# Prototype_Board.net
KiCad netlist of a schematic drawn in EAGLE
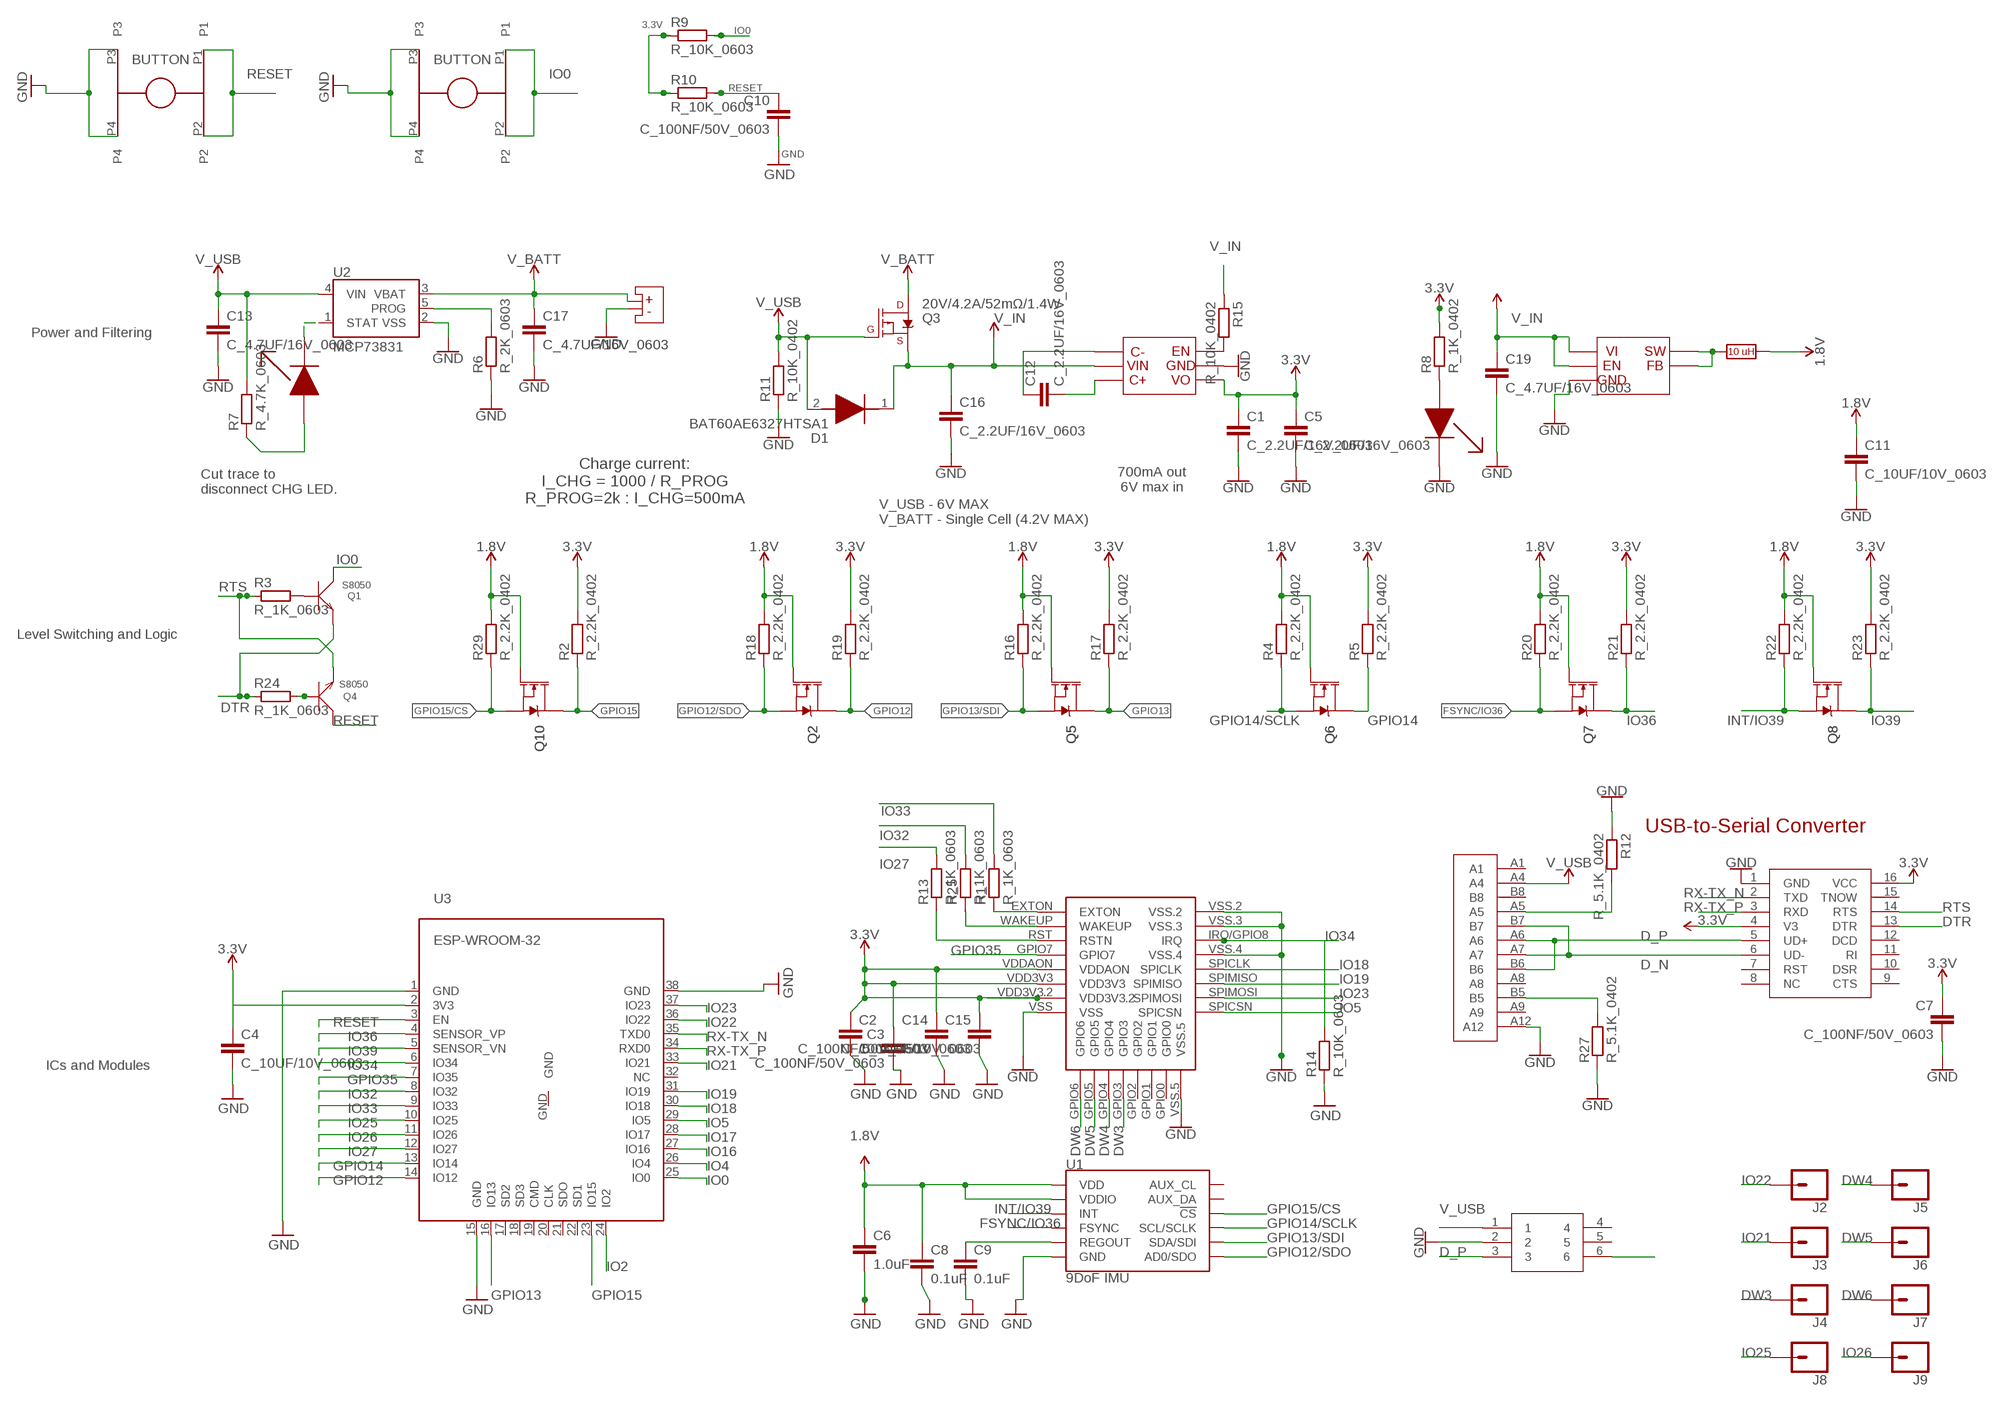
[diagram p0: schematic, sheet 1]

(export (version "E")
  (design (tool "Eeschema 10.0.6"))
  (components
    (comp (ref "C1")
      (value "C_2.2UF/16V_0603")
      (footprint "eagle-import:C0603")
      (fields (field (name "LCSC_PART") "C23630"))
      (libsource (lib "eagle-import") (part "C__06032.2UF/16V"))
    )
    (comp (ref "C2")
      (value "C_10UF/10V_0603")
      (footprint "eagle-import:C0603")
      (fields (field (name "LCSC_PART") "C19702"))
      (libsource (lib "eagle-import") (part "C__060310UF/10V"))
    )
    (comp (ref "C3")
      (value "C_100NF/50V_0603")
      (footprint "eagle-import:C0603")
      (fields (field (name "LCSC_PART") "C14663"))
      (libsource (lib "eagle-import") (part "C__0603100NF/50V"))
    )
    (comp (ref "C4")
      (value "C_10UF/10V_0603")
      (footprint "eagle-import:C0603")
      (fields (field (name "LCSC_PART") "C19702"))
      (libsource (lib "eagle-import") (part "C__060310UF/10V"))
    )
    (comp (ref "C5")
      (value "C_2.2UF/16V_0603")
      (footprint "eagle-import:C0603")
      (fields (field (name "LCSC_PART") "C23630"))
      (libsource (lib "eagle-import") (part "C__06032.2UF/16V"))
    )
    (comp (ref "C6")
      (value "1.0uF")
      (footprint "eagle-import:0603")
      (libsource (lib "eagle-import") (part "1.0UF-0603-16V-10%-X7R"))
    )
    (comp (ref "C7")
      (value "C_100NF/50V_0603")
      (footprint "eagle-import:C0603")
      (fields (field (name "LCSC_PART") "C14663"))
      (libsource (lib "eagle-import") (part "C__0603100NF/50V"))
    )
    (comp (ref "C8")
      (value "0.1uF")
      (footprint "eagle-import:0603")
      (libsource (lib "eagle-import") (part "0.1UF-0603-25V-5%"))
    )
    (comp (ref "C9")
      (value "0.1uF")
      (footprint "eagle-import:0603")
      (libsource (lib "eagle-import") (part "0.1UF-0603-25V-5%"))
    )
    (comp (ref "C10")
      (value "C_100NF/50V_0603")
      (footprint "eagle-import:C0603")
      (fields (field (name "LCSC_PART") "C14663"))
      (libsource (lib "eagle-import") (part "C__0603100NF/50V"))
    )
    (comp (ref "C11")
      (value "C_10UF/10V_0603")
      (footprint "eagle-import:C0603")
      (fields (field (name "LCSC_PART") "C19702"))
      (libsource (lib "eagle-import") (part "C__060310UF/10V"))
    )
    (comp (ref "C12")
      (value "C_2.2UF/16V_0603")
      (footprint "eagle-import:C0603")
      (fields (field (name "LCSC_PART") "C23630"))
      (libsource (lib "eagle-import") (part "C__06032.2UF/16V"))
    )
    (comp (ref "C13")
      (value "C_4.7UF/16V_0603")
      (footprint "eagle-import:C0603")
      (fields (field (name "LCSC_PART") "C19666"))
      (libsource (lib "eagle-import") (part "C__06034.7UF/16V"))
    )
    (comp (ref "C14")
      (value "C_100NF/50V_0603")
      (footprint "eagle-import:C0603")
      (fields (field (name "LCSC_PART") "C14663"))
      (libsource (lib "eagle-import") (part "C__0603100NF/50V"))
    )
    (comp (ref "C15")
      (value "C_100NF/50V_0603")
      (footprint "eagle-import:C0603")
      (fields (field (name "LCSC_PART") "C14663"))
      (libsource (lib "eagle-import") (part "C__0603100NF/50V"))
    )
    (comp (ref "C16")
      (value "C_2.2UF/16V_0603")
      (footprint "eagle-import:C0603")
      (fields (field (name "LCSC_PART") "C23630"))
      (libsource (lib "eagle-import") (part "C__06032.2UF/16V"))
    )
    (comp (ref "C17")
      (value "C_4.7UF/16V_0603")
      (footprint "eagle-import:C0603")
      (fields (field (name "LCSC_PART") "C19666"))
      (libsource (lib "eagle-import") (part "C__06034.7UF/16V"))
    )
    (comp (ref "C19")
      (value "C_4.7UF/16V_0603")
      (footprint "eagle-import:C0603")
      (fields (field (name "LCSC_PART") "C19666"))
      (libsource (lib "eagle-import") (part "C__06034.7UF/16V"))
    )
    (comp (ref "D1")
      (value "BAT60AE6327HTSA1")
      (footprint "eagle-import:SOD2513X110N")
      (fields (field (name "MOUSER_PART_NUMBER") "726-BAT60AE6327HTSA1"))
      (libsource (lib "eagle-import") (part "BAT60AE6327HTSA1"))
    )
    (comp (ref "J2")
      (value "CONN_01PTH_2MM")
      (footprint "eagle-import:1X01_2MM")
      (libsource (lib "eagle-import") (part "CONN_01PTH_2MM"))
    )
    (comp (ref "J3")
      (value "CONN_01PTH_2MM")
      (footprint "eagle-import:1X01_2MM")
      (libsource (lib "eagle-import") (part "CONN_01PTH_2MM"))
    )
    (comp (ref "J4")
      (value "CONN_01PTH_2MM")
      (footprint "eagle-import:1X01_2MM")
      (libsource (lib "eagle-import") (part "CONN_01PTH_2MM"))
    )
    (comp (ref "J5")
      (value "CONN_01PTH_2MM")
      (footprint "eagle-import:1X01_2MM")
      (libsource (lib "eagle-import") (part "CONN_01PTH_2MM"))
    )
    (comp (ref "J6")
      (value "CONN_01PTH_2MM")
      (footprint "eagle-import:1X01_2MM")
      (libsource (lib "eagle-import") (part "CONN_01PTH_2MM"))
    )
    (comp (ref "J7")
      (value "CONN_01PTH_2MM")
      (footprint "eagle-import:1X01_2MM")
      (libsource (lib "eagle-import") (part "CONN_01PTH_2MM"))
    )
    (comp (ref "J8")
      (value "CONN_01PTH_2MM")
      (footprint "eagle-import:1X01_2MM")
      (libsource (lib "eagle-import") (part "CONN_01PTH_2MM"))
    )
    (comp (ref "J9")
      (value "CONN_01PTH_2MM")
      (footprint "eagle-import:1X01_2MM")
      (libsource (lib "eagle-import") (part "CONN_01PTH_2MM"))
    )
    (comp (ref "Q1")
      (value "S8050")
      (footprint "eagle-import:SOT23")
      (libsource (lib "eagle-import") (part "TRANSISTOR-NPN-SOT23"))
    )
    (comp (ref "Q2")
      (value "20V/0.2A/8MHz/1.2Ω/1Vth")
      (footprint "eagle-import:SOT-416FL")
      (libsource (lib "eagle-import") (part "MOSFET-NCH-RE1C002UN"))
    )
    (comp (ref "Q3")
      (value "20V/4.2A/52mΩ/1.4W")
      (footprint "eagle-import:SOT23-3@1")
      (libsource (lib "eagle-import") (part "MOSFET_PCH-DMG2305UX-7"))
    )
    (comp (ref "Q4")
      (value "S8050")
      (footprint "eagle-import:SOT23")
      (libsource (lib "eagle-import") (part "TRANSISTOR-NPN-SOT23"))
    )
    (comp (ref "Q5")
      (value "20V/0.2A/8MHz/1.2Ω/1Vth")
      (footprint "eagle-import:SOT-416FL")
      (libsource (lib "eagle-import") (part "MOSFET-NCH-RE1C002UN"))
    )
    (comp (ref "Q6")
      (value "20V/0.2A/8MHz/1.2Ω/1Vth")
      (footprint "eagle-import:SOT-416FL")
      (libsource (lib "eagle-import") (part "MOSFET-NCH-RE1C002UN"))
    )
    (comp (ref "Q7")
      (value "20V/0.2A/8MHz/1.2Ω/1Vth")
      (footprint "eagle-import:SOT-416FL")
      (libsource (lib "eagle-import") (part "MOSFET-NCH-RE1C002UN"))
    )
    (comp (ref "Q8")
      (value "20V/0.2A/8MHz/1.2Ω/1Vth")
      (footprint "eagle-import:SOT-416FL")
      (libsource (lib "eagle-import") (part "MOSFET-NCH-RE1C002UN"))
    )
    (comp (ref "Q10")
      (value "20V/0.2A/8MHz/1.2Ω/1Vth")
      (footprint "eagle-import:SOT-416FL")
      (libsource (lib "eagle-import") (part "MOSFET-NCH-RE1C002UN"))
    )
    (comp (ref "R1")
      (value "R_1K_0603")
      (footprint "eagle-import:R0603")
      (fields (field (name "LCSC_PART") "C21190"))
      (libsource (lib "eagle-import") (part "R__06031K"))
    )
    (comp (ref "R2")
      (value "R_2.2K_0402")
      (footprint "eagle-import:R0402")
      (fields (field (name "LCSC_PART") "C25879"))
      (libsource (lib "eagle-import") (part "R__04022.2K"))
    )
    (comp (ref "R3")
      (value "R_1K_0603")
      (footprint "eagle-import:R0603")
      (fields (field (name "LCSC_PART") "C21190"))
      (libsource (lib "eagle-import") (part "R__06031K"))
    )
    (comp (ref "R4")
      (value "R_2.2K_0402")
      (footprint "eagle-import:R0402")
      (fields (field (name "LCSC_PART") "C25879"))
      (libsource (lib "eagle-import") (part "R__04022.2K"))
    )
    (comp (ref "R5")
      (value "R_2.2K_0402")
      (footprint "eagle-import:R0402")
      (fields (field (name "LCSC_PART") "C25879"))
      (libsource (lib "eagle-import") (part "R__04022.2K"))
    )
    (comp (ref "R6")
      (value "R_2K_0603")
      (footprint "eagle-import:R0603")
      (fields (field (name "LCSC_PART") "C22975"))
      (libsource (lib "eagle-import") (part "R__06032K"))
    )
    (comp (ref "R7")
      (value "R_4.7K_0603")
      (footprint "eagle-import:R0603")
      (fields (field (name "LCSC_PART") "C23162"))
      (libsource (lib "eagle-import") (part "R__06034.7K"))
    )
    (comp (ref "R8")
      (value "R_1K_0402")
      (footprint "eagle-import:R0402")
      (fields (field (name "LCSC_PART") "C11702"))
      (libsource (lib "eagle-import") (part "R__04021K"))
    )
    (comp (ref "R9")
      (value "R_10K_0603")
      (footprint "eagle-import:R0603")
      (fields (field (name "LCSC_PART") "C25804"))
      (libsource (lib "eagle-import") (part "R__060310K"))
    )
    (comp (ref "R10")
      (value "R_10K_0603")
      (footprint "eagle-import:R0603")
      (fields (field (name "LCSC_PART") "C25804"))
      (libsource (lib "eagle-import") (part "R__060310K"))
    )
    (comp (ref "R11")
      (value "R_10K_0402")
      (footprint "eagle-import:R0402")
      (fields (field (name "LCSC_PART") "C25744"))
      (libsource (lib "eagle-import") (part "R__040210K"))
    )
    (comp (ref "R12")
      (value "R_5.1K_0402")
      (footprint "eagle-import:R0402")
      (fields (field (name "LCSC_PART") "C25905"))
      (libsource (lib "eagle-import") (part "R__04025.1K"))
    )
    (comp (ref "R13")
      (value "R_1K_0603")
      (footprint "eagle-import:R0603")
      (fields (field (name "LCSC_PART") "C21190"))
      (libsource (lib "eagle-import") (part "R__06031K"))
    )
    (comp (ref "R14")
      (value "R_10K_0603")
      (footprint "eagle-import:R0603")
      (fields (field (name "LCSC_PART") "C25804"))
      (libsource (lib "eagle-import") (part "R__060310K"))
    )
    (comp (ref "R15")
      (value "R_10K_0402")
      (footprint "eagle-import:R0402")
      (fields (field (name "LCSC_PART") "C25744"))
      (libsource (lib "eagle-import") (part "R__040210K"))
    )
    (comp (ref "R16")
      (value "R_2.2K_0402")
      (footprint "eagle-import:R0402")
      (fields (field (name "LCSC_PART") "C25879"))
      (libsource (lib "eagle-import") (part "R__04022.2K"))
    )
    (comp (ref "R17")
      (value "R_2.2K_0402")
      (footprint "eagle-import:R0402")
      (fields (field (name "LCSC_PART") "C25879"))
      (libsource (lib "eagle-import") (part "R__04022.2K"))
    )
    (comp (ref "R18")
      (value "R_2.2K_0402")
      (footprint "eagle-import:R0402")
      (fields (field (name "LCSC_PART") "C25879"))
      (libsource (lib "eagle-import") (part "R__04022.2K"))
    )
    (comp (ref "R19")
      (value "R_2.2K_0402")
      (footprint "eagle-import:R0402")
      (fields (field (name "LCSC_PART") "C25879"))
      (libsource (lib "eagle-import") (part "R__04022.2K"))
    )
    (comp (ref "R20")
      (value "R_2.2K_0402")
      (footprint "eagle-import:R0402")
      (fields (field (name "LCSC_PART") "C25879"))
      (libsource (lib "eagle-import") (part "R__04022.2K"))
    )
    (comp (ref "R21")
      (value "R_2.2K_0402")
      (footprint "eagle-import:R0402")
      (fields (field (name "LCSC_PART") "C25879"))
      (libsource (lib "eagle-import") (part "R__04022.2K"))
    )
    (comp (ref "R22")
      (value "R_2.2K_0402")
      (footprint "eagle-import:R0402")
      (fields (field (name "LCSC_PART") "C25879"))
      (libsource (lib "eagle-import") (part "R__04022.2K"))
    )
    (comp (ref "R23")
      (value "R_2.2K_0402")
      (footprint "eagle-import:R0402")
      (fields (field (name "LCSC_PART") "C25879"))
      (libsource (lib "eagle-import") (part "R__04022.2K"))
    )
    (comp (ref "R24")
      (value "R_1K_0603")
      (footprint "eagle-import:R0603")
      (fields (field (name "LCSC_PART") "C21190"))
      (libsource (lib "eagle-import") (part "R__06031K"))
    )
    (comp (ref "R25")
      (value "R_1K_0603")
      (footprint "eagle-import:R0603")
      (fields (field (name "LCSC_PART") "C21190"))
      (libsource (lib "eagle-import") (part "R__06031K"))
    )
    (comp (ref "R27")
      (value "R_5.1K_0402")
      (footprint "eagle-import:R0402")
      (fields (field (name "LCSC_PART") "C25905"))
      (libsource (lib "eagle-import") (part "R__04025.1K"))
    )
    (comp (ref "R29")
      (value "R_2.2K_0402")
      (footprint "eagle-import:R0402")
      (fields (field (name "LCSC_PART") "C25879"))
      (libsource (lib "eagle-import") (part "R__04022.2K"))
    )
    (comp (ref "U$1")
      (value "K2-6639SP-C4SC-04_C83206")
      (footprint "eagle-import:K2-6639SP-C4SC-04")
      (libsource (lib "eagle-import") (part "K2-6639SP-C4SC-04_C83206"))
    )
    (comp (ref "U$2")
      (value "MLF2012")
      (footprint "eagle-import:MLF2012")
      (libsource (lib "eagle-import") (part "MLF2012"))
    )
    (comp (ref "U$3")
      (value "K2-6639SP-C4SC-04_C83206")
      (footprint "eagle-import:K2-6639SP-C4SC-04")
      (libsource (lib "eagle-import") (part "K2-6639SP-C4SC-04_C83206"))
    )
    (comp (ref "U$4")
      (value "TPS62202DBVR")
      (footprint "eagle-import:TPS62202DBVR")
      (libsource (lib "eagle-import") (part "TPS62202DBVR"))
    )
    (comp (ref "U$5")
      (value "HE9008M6R")
      (footprint "eagle-import:HE9008M6R")
      (libsource (lib "eagle-import") (part "HE9008M6R"))
    )
    (comp (ref "U$6")
      (value "19-217/GHC-YR1S2/3T")
      (footprint "eagle-import:19-217_GHC-YR1S2_3T")
      (libsource (lib "eagle-import") (part "19-217/GHC-YR1S2/3T"))
    )
    (comp (ref "U$7")
      (value "TPSMF05CT1G")
      (footprint "eagle-import:TPSMF05CT1G")
      (libsource (lib "eagle-import") (part "TPSMF05CT1G"))
    )
    (comp (ref "U$8")
      (value "SM02B_PASS_TB_LF")
      (footprint "eagle-import:SM02B_PASS_TB_LF")
      (libsource (lib "eagle-import") (part "SM02B_PASS_TB_LF"))
    )
    (comp (ref "U$9")
      (value "19-217/GHC-YR1S2/3T")
      (footprint "eagle-import:19-217_GHC-YR1S2_3T")
      (libsource (lib "eagle-import") (part "19-217/GHC-YR1S2/3T"))
    )
    (comp (ref "U$10")
      (value "USBC19")
      (footprint "eagle-import:USBC19")
      (libsource (lib "eagle-import") (part "USBC19"))
    )
    (comp (ref "U$11")
      (value "CH340B")
      (footprint "eagle-import:SOP-16")
      (libsource (lib "eagle-import") (part "CH340B"))
    )
    (comp (ref "U1")
      (value "9DoF IMU")
      (footprint "eagle-import:QFN24-3X3")
      (libsource (lib "eagle-import") (part "ICM-20948"))
    )
    (comp (ref "U2")
      (value "MCP73831")
      (footprint "eagle-import:SOT23-5")
      (libsource (lib "eagle-import") (part "MCP73831"))
    )
    (comp (ref "U3")
      (value "ESP-WROOM-32")
      (footprint "eagle-import:ESP-WROOM-32")
      (libsource (lib "eagle-import") (part "ESP-WROOM-32"))
    )
    (comp (ref "U5")
      (value "DWM1000")
      (footprint "eagle-import:DWM1000")
      (libsource (lib "eagle-import") (part "DWM1000"))
    )
  )
  (nets
    (net (code "1") (name "/DTR") (class "Default")
      (node (ref "Q1") (pin "2") (pinfunction "E_2") (pintype "passive"))
      (node (ref "R24") (pin "1") (pinfunction "1_1") (pintype "passive"))
      (node (ref "U$11") (pin "13") (pinfunction "DTR_13") (pintype "bidirectional"))
    )
    (net (code "2") (name "/DW3") (class "Default")
      (node (ref "J4") (pin "1") (pinfunction "1_1") (pintype "passive"))
      (node (ref "U5") (pin "GPIO3") (pinfunction "GPIO3_GPIO3") (pintype "bidirectional"))
    )
    (net (code "3") (name "/DW4") (class "Default")
      (node (ref "J5") (pin "1") (pinfunction "1_1") (pintype "passive"))
      (node (ref "U5") (pin "GPIO4") (pinfunction "GPIO4_GPIO4") (pintype "bidirectional"))
    )
    (net (code "4") (name "/DW5") (class "Default")
      (node (ref "J6") (pin "1") (pinfunction "1_1") (pintype "passive"))
      (node (ref "U5") (pin "GPIO5") (pinfunction "GPIO5_GPIO5") (pintype "bidirectional"))
    )
    (net (code "5") (name "/DW6") (class "Default")
      (node (ref "J7") (pin "1") (pinfunction "1_1") (pintype "passive"))
      (node (ref "U5") (pin "GPIO6") (pinfunction "GPIO6_GPIO6") (pintype "bidirectional"))
    )
    (net (code "6") (name "/D_N") (class "Default")
      (node (ref "U$10") (pin "A7") (pinfunction "A7_A7") (pintype "bidirectional"))
      (node (ref "U$10") (pin "B7") (pinfunction "B7_B7") (pintype "bidirectional"))
      (node (ref "U$11") (pin "6") (pinfunction "UD-_6") (pintype "bidirectional"))
      (node (ref "U$7") (pin "6") (pinfunction "6_6") (pintype "bidirectional"))
    )
    (net (code "7") (name "/D_P") (class "Default")
      (node (ref "U$10") (pin "A6") (pinfunction "A6_A6") (pintype "bidirectional"))
      (node (ref "U$10") (pin "B6") (pinfunction "B6_B6") (pintype "bidirectional"))
      (node (ref "U$11") (pin "5") (pinfunction "UD+_5") (pintype "bidirectional"))
      (node (ref "U$7") (pin "3") (pinfunction "3_3") (pintype "bidirectional"))
    )
    (net (code "8") (name "/GPIO14") (class "Default")
      (node (ref "Q6") (pin "3") (pinfunction "D_3") (pintype "bidirectional"))
      (node (ref "R5") (pin "1") (pinfunction "1_1") (pintype "passive"))
      (node (ref "U3") (pin "13") (pinfunction "IO14_13") (pintype "bidirectional"))
    )
    (net (code "9") (name "/GPIO14{slash}SCLK") (class "Default")
      (node (ref "Q6") (pin "2") (pinfunction "S_2") (pintype "bidirectional"))
      (node (ref "R4") (pin "1") (pinfunction "1_1") (pintype "passive"))
      (node (ref "U1") (pin "23") (pinfunction "SCL/SCLK_23") (pintype "bidirectional"))
    )
    (net (code "10") (name "/GPIO35") (class "Default")
      (node (ref "U3") (pin "7") (pinfunction "IO35_7") (pintype "bidirectional"))
      (node (ref "U5") (pin "GPIO7") (pinfunction "GPIO7_GPIO7") (pintype "bidirectional"))
    )
    (net (code "11") (name "/INT{slash}IO39") (class "Default")
      (node (ref "Q8") (pin "2") (pinfunction "S_2") (pintype "bidirectional"))
      (node (ref "R22") (pin "1") (pinfunction "1_1") (pintype "passive"))
      (node (ref "U1") (pin "12") (pinfunction "INT_12") (pintype "bidirectional"))
    )
    (net (code "12") (name "/IO0") (class "Default")
      (node (ref "Q1") (pin "3") (pinfunction "C_3") (pintype "passive"))
      (node (ref "R9") (pin "2") (pinfunction "2_2") (pintype "passive"))
      (node (ref "U$3") (pin "P1") (pinfunction "P1_P1") (pintype "bidirectional"))
      (node (ref "U$3") (pin "P2") (pinfunction "P2_P2") (pintype "bidirectional"))
      (node (ref "U3") (pin "25") (pinfunction "IO0_25") (pintype "bidirectional"))
    )
    (net (code "13") (name "/IO2") (class "Default")
      (node (ref "U3") (pin "24") (pinfunction "IO2_24") (pintype "bidirectional"))
    )
    (net (code "14") (name "/IO4") (class "Default")
      (node (ref "U3") (pin "26") (pinfunction "IO4_26") (pintype "bidirectional"))
    )
    (net (code "15") (name "/IO5") (class "Default")
      (node (ref "U3") (pin "29") (pinfunction "IO5_29") (pintype "bidirectional"))
      (node (ref "U5") (pin "SPICSN") (pinfunction "SPICSN_SPICSN") (pintype "bidirectional"))
    )
    (net (code "16") (name "/IO16") (class "Default")
      (node (ref "U3") (pin "27") (pinfunction "IO16_27") (pintype "bidirectional"))
    )
    (net (code "17") (name "/IO17") (class "Default")
      (node (ref "U3") (pin "28") (pinfunction "IO17_28") (pintype "bidirectional"))
    )
    (net (code "18") (name "/IO18") (class "Default")
      (node (ref "U3") (pin "30") (pinfunction "IO18_30") (pintype "bidirectional"))
      (node (ref "U5") (pin "SPICLK") (pinfunction "SPICLK_SPICLK") (pintype "bidirectional"))
    )
    (net (code "19") (name "/IO19") (class "Default")
      (node (ref "U3") (pin "31") (pinfunction "IO19_31") (pintype "bidirectional"))
      (node (ref "U5") (pin "SPIMISO") (pinfunction "SPIMISO_SPIMISO") (pintype "bidirectional"))
    )
    (net (code "20") (name "/IO21") (class "Default")
      (node (ref "J3") (pin "1") (pinfunction "1_1") (pintype "passive"))
      (node (ref "U3") (pin "33") (pinfunction "IO21_33") (pintype "bidirectional"))
    )
    (net (code "21") (name "/IO22") (class "Default")
      (node (ref "J2") (pin "1") (pinfunction "1_1") (pintype "passive"))
      (node (ref "U3") (pin "36") (pinfunction "IO22_36") (pintype "bidirectional"))
    )
    (net (code "22") (name "/IO23") (class "Default")
      (node (ref "U3") (pin "37") (pinfunction "IO23_37") (pintype "bidirectional"))
      (node (ref "U5") (pin "SPIMOSI") (pinfunction "SPIMOSI_SPIMOSI") (pintype "bidirectional"))
    )
    (net (code "23") (name "/IO25") (class "Default")
      (node (ref "J8") (pin "1") (pinfunction "1_1") (pintype "passive"))
      (node (ref "U3") (pin "10") (pinfunction "IO25_10") (pintype "bidirectional"))
    )
    (net (code "24") (name "/IO26") (class "Default")
      (node (ref "J9") (pin "1") (pinfunction "1_1") (pintype "passive"))
      (node (ref "U3") (pin "11") (pinfunction "IO26_11") (pintype "bidirectional"))
    )
    (net (code "25") (name "/IO27") (class "Default")
      (node (ref "R13") (pin "2") (pinfunction "2_2") (pintype "passive"))
      (node (ref "U3") (pin "12") (pinfunction "IO27_12") (pintype "bidirectional"))
    )
    (net (code "26") (name "/IO32") (class "Default")
      (node (ref "R25") (pin "2") (pinfunction "2_2") (pintype "passive"))
      (node (ref "U3") (pin "8") (pinfunction "IO32_8") (pintype "bidirectional"))
    )
    (net (code "27") (name "/IO33") (class "Default")
      (node (ref "R1") (pin "2") (pinfunction "2_2") (pintype "passive"))
      (node (ref "U3") (pin "9") (pinfunction "IO33_9") (pintype "bidirectional"))
    )
    (net (code "28") (name "/IO34") (class "Default")
      (node (ref "R14") (pin "2") (pinfunction "2_2") (pintype "passive"))
      (node (ref "U3") (pin "6") (pinfunction "IO34_6") (pintype "bidirectional"))
      (node (ref "U5") (pin "IRQ/GPIO8") (pinfunction "IRQ_IRQ/GPIO8") (pintype "bidirectional"))
    )
    (net (code "29") (name "/IO36") (class "Default")
      (node (ref "Q7") (pin "3") (pinfunction "D_3") (pintype "bidirectional"))
      (node (ref "R21") (pin "1") (pinfunction "1_1") (pintype "passive"))
      (node (ref "U3") (pin "4") (pinfunction "SENSOR_VP_4") (pintype "bidirectional"))
    )
    (net (code "30") (name "/IO39") (class "Default")
      (node (ref "Q8") (pin "3") (pinfunction "D_3") (pintype "bidirectional"))
      (node (ref "R23") (pin "1") (pinfunction "1_1") (pintype "passive"))
      (node (ref "U3") (pin "5") (pinfunction "SENSOR_VN_5") (pintype "bidirectional"))
    )
    (net (code "31") (name "/RESET") (class "Default")
      (node (ref "C10") (pin "1") (pinfunction "1_1") (pintype "passive"))
      (node (ref "Q4") (pin "3") (pinfunction "C_3") (pintype "passive"))
      (node (ref "R10") (pin "2") (pinfunction "2_2") (pintype "passive"))
      (node (ref "U$1") (pin "P1") (pinfunction "P1_P1") (pintype "bidirectional"))
      (node (ref "U$1") (pin "P2") (pinfunction "P2_P2") (pintype "bidirectional"))
      (node (ref "U3") (pin "3") (pinfunction "EN_3") (pintype "bidirectional"))
    )
    (net (code "32") (name "/RTS") (class "Default")
      (node (ref "Q4") (pin "2") (pinfunction "E_2") (pintype "passive"))
      (node (ref "R3") (pin "1") (pinfunction "1_1") (pintype "passive"))
      (node (ref "U$11") (pin "14") (pinfunction "RTS_14") (pintype "bidirectional"))
    )
    (net (code "33") (name "/RX-TX_N") (class "Default")
      (node (ref "U$11") (pin "2") (pinfunction "TXD_2") (pintype "bidirectional"))
      (node (ref "U3") (pin "35") (pinfunction "TXD0_35") (pintype "bidirectional"))
    )
    (net (code "34") (name "/RX-TX_P") (class "Default")
      (node (ref "U$11") (pin "3") (pinfunction "RXD_3") (pintype "bidirectional"))
      (node (ref "U3") (pin "34") (pinfunction "RXD0_34") (pintype "bidirectional"))
    )
    (net (code "35") (name "1.8V") (class "Default")
      (node (ref "C11") (pin "1") (pinfunction "1_1") (pintype "passive"))
      (node (ref "C6") (pin "1") (pinfunction "1_1") (pintype "passive"))
      (node (ref "C8") (pin "1") (pinfunction "1_1") (pintype "passive"))
      (node (ref "Q10") (pin "1") (pinfunction "G_1") (pintype "bidirectional"))
      (node (ref "Q2") (pin "1") (pinfunction "G_1") (pintype "bidirectional"))
      (node (ref "Q5") (pin "1") (pinfunction "G_1") (pintype "bidirectional"))
      (node (ref "Q6") (pin "1") (pinfunction "G_1") (pintype "bidirectional"))
      (node (ref "Q7") (pin "1") (pinfunction "G_1") (pintype "bidirectional"))
      (node (ref "Q8") (pin "1") (pinfunction "G_1") (pintype "bidirectional"))
      (node (ref "R16") (pin "2") (pinfunction "2_2") (pintype "passive"))
      (node (ref "R18") (pin "2") (pinfunction "2_2") (pintype "passive"))
      (node (ref "R20") (pin "2") (pinfunction "2_2") (pintype "passive"))
      (node (ref "R22") (pin "2") (pinfunction "2_2") (pintype "passive"))
      (node (ref "R29") (pin "2") (pinfunction "2_2") (pintype "passive"))
      (node (ref "R4") (pin "2") (pinfunction "2_2") (pintype "passive"))
      (node (ref "U$2") (pin "2") (pinfunction "P$2_2") (pintype "bidirectional"))
      (node (ref "U1") (pin "13") (pinfunction "VDD_13") (pintype "bidirectional"))
      (node (ref "U1") (pin "8") (pinfunction "VDDIO_8") (pintype "bidirectional"))
    )
    (net (code "36") (name "3.3V") (class "Default")
      (node (ref "C1") (pin "1") (pinfunction "1_1") (pintype "passive"))
      (node (ref "C14") (pin "1") (pinfunction "1_1") (pintype "passive"))
      (node (ref "C15") (pin "1") (pinfunction "1_1") (pintype "passive"))
      (node (ref "C2") (pin "1") (pinfunction "1_1") (pintype "passive"))
      (node (ref "C3") (pin "1") (pinfunction "1_1") (pintype "passive"))
      (node (ref "C4") (pin "1") (pinfunction "1_1") (pintype "passive"))
      (node (ref "C5") (pin "1") (pinfunction "1_1") (pintype "passive"))
      (node (ref "C7") (pin "1") (pinfunction "1_1") (pintype "passive"))
      (node (ref "R10") (pin "1") (pinfunction "1_1") (pintype "passive"))
      (node (ref "R17") (pin "2") (pinfunction "2_2") (pintype "passive"))
      (node (ref "R19") (pin "2") (pinfunction "2_2") (pintype "passive"))
      (node (ref "R2") (pin "2") (pinfunction "2_2") (pintype "passive"))
      (node (ref "R21") (pin "2") (pinfunction "2_2") (pintype "passive"))
      (node (ref "R23") (pin "2") (pinfunction "2_2") (pintype "passive"))
      (node (ref "R5") (pin "2") (pinfunction "2_2") (pintype "passive"))
      (node (ref "R8") (pin "2") (pinfunction "2_2") (pintype "passive"))
      (node (ref "R9") (pin "1") (pinfunction "1_1") (pintype "passive"))
      (node (ref "U$11") (pin "16") (pinfunction "VCC_16") (pintype "bidirectional"))
      (node (ref "U$11") (pin "4") (pinfunction "V3_4") (pintype "bidirectional"))
      (node (ref "U$5") (pin "VOUT") (pinfunction "VO_VOUT") (pintype "bidirectional"))
      (node (ref "U3") (pin "2") (pinfunction "3V3_2") (pintype "bidirectional"))
      (node (ref "U5") (pin "VDD3V3") (pinfunction "VDD3V3_VDD3V3") (pintype "bidirectional"))
      (node (ref "U5") (pin "VDD3V3.2") (pinfunction "VDD3V3.2_VDD3V3.2") (pintype "bidirectional"))
      (node (ref "U5") (pin "VDDAON") (pinfunction "VDDAON_VDDAON") (pintype "bidirectional"))
    )
    (net (code "37") (name "FSYNC{slash}IO36") (class "Default")
      (node (ref "Q7") (pin "2") (pinfunction "S_2") (pintype "bidirectional"))
      (node (ref "R20") (pin "1") (pinfunction "1_1") (pintype "passive"))
      (node (ref "U1") (pin "11") (pinfunction "FSYNC_11") (pintype "bidirectional"))
    )
    (net (code "38") (name "GND") (class "Default")
      (node (ref "C1") (pin "2") (pinfunction "2_2") (pintype "passive"))
      (node (ref "C10") (pin "2") (pinfunction "2_2") (pintype "passive"))
      (node (ref "C11") (pin "2") (pinfunction "2_2") (pintype "passive"))
      (node (ref "C13") (pin "2") (pinfunction "2_2") (pintype "passive"))
      (node (ref "C14") (pin "2") (pinfunction "2_2") (pintype "passive"))
      (node (ref "C15") (pin "2") (pinfunction "2_2") (pintype "passive"))
      (node (ref "C16") (pin "2") (pinfunction "2_2") (pintype "passive"))
      (node (ref "C17") (pin "2") (pinfunction "2_2") (pintype "passive"))
      (node (ref "C19") (pin "2") (pinfunction "2_2") (pintype "passive"))
      (node (ref "C2") (pin "2") (pinfunction "2_2") (pintype "passive"))
      (node (ref "C3") (pin "2") (pinfunction "2_2") (pintype "passive"))
      (node (ref "C4") (pin "2") (pinfunction "2_2") (pintype "passive"))
      (node (ref "C5") (pin "2") (pinfunction "2_2") (pintype "passive"))
      (node (ref "C6") (pin "2") (pinfunction "2_2") (pintype "passive"))
      (node (ref "C7") (pin "2") (pinfunction "2_2") (pintype "passive"))
      (node (ref "C8") (pin "2") (pinfunction "2_2") (pintype "passive"))
      (node (ref "C9") (pin "2") (pinfunction "2_2") (pintype "passive"))
      (node (ref "R11") (pin "1") (pinfunction "1_1") (pintype "passive"))
      (node (ref "R12") (pin "1") (pinfunction "1_1") (pintype "passive"))
      (node (ref "R14") (pin "1") (pinfunction "1_1") (pintype "passive"))
      (node (ref "R27") (pin "1") (pinfunction "1_1") (pintype "passive"))
      (node (ref "R6") (pin "1") (pinfunction "1_1") (pintype "passive"))
      (node (ref "U$1") (pin "P3") (pinfunction "P3_P3") (pintype "bidirectional"))
      (node (ref "U$1") (pin "P4") (pinfunction "P4_P4") (pintype "bidirectional"))
      (node (ref "U$10") (pin "A12") (pinfunction "A12_A12") (pintype "bidirectional"))
      (node (ref "U$11") (pin "1") (pinfunction "GND_1") (pintype "bidirectional"))
      (node (ref "U$3") (pin "P3") (pinfunction "P3_P3") (pintype "bidirectional"))
      (node (ref "U$3") (pin "P4") (pinfunction "P4_P4") (pintype "bidirectional"))
      (node (ref "U$4") (pin "2") (pinfunction "GND_2") (pintype "bidirectional"))
      (node (ref "U$5") (pin "GND") (pinfunction "GND_GND") (pintype "bidirectional"))
      (node (ref "U$7") (pin "2") (pinfunction "2_2") (pintype "bidirectional"))
      (node (ref "U$8") (pin "3") (pinfunction "-_3") (pintype "bidirectional"))
      (node (ref "U$9") (pin "2") (pinfunction "2_2") (pintype "bidirectional"))
      (node (ref "U1") (pin "18") (pinfunction "GND_18") (pintype "bidirectional"))
      (node (ref "U1") (pin "20") (pinfunction "GND_20") (pintype "bidirectional"))
      (node (ref "U2") (pin "2") (pinfunction "VSS_2") (pintype "power_in"))
      (node (ref "U3") (pin "1") (pinfunction "GND_1") (pintype "bidirectional"))
      (node (ref "U3") (pin "15") (pinfunction "GND_15") (pintype "bidirectional"))
      (node (ref "U3") (pin "38") (pinfunction "GND_38") (pintype "bidirectional"))
      (node (ref "U5") (pin "VSS") (pinfunction "VSS_VSS") (pintype "bidirectional"))
      (node (ref "U5") (pin "VSS.2") (pinfunction "VSS.2_VSS.2") (pintype "bidirectional"))
      (node (ref "U5") (pin "VSS.3") (pinfunction "VSS.3_VSS.3") (pintype "bidirectional"))
      (node (ref "U5") (pin "VSS.4") (pinfunction "VSS.4_VSS.4") (pintype "bidirectional"))
      (node (ref "U5") (pin "VSS.5") (pinfunction "VSS.5_VSS.5") (pintype "bidirectional"))
    )
    (net (code "39") (name "GPIO12") (class "Default")
      (node (ref "Q2") (pin "3") (pinfunction "D_3") (pintype "bidirectional"))
      (node (ref "R19") (pin "1") (pinfunction "1_1") (pintype "passive"))
      (node (ref "U3") (pin "14") (pinfunction "IO12_14") (pintype "bidirectional"))
    )
    (net (code "40") (name "GPIO12{slash}SDO") (class "Default")
      (node (ref "Q2") (pin "2") (pinfunction "S_2") (pintype "bidirectional"))
      (node (ref "R18") (pin "1") (pinfunction "1_1") (pintype "passive"))
      (node (ref "U1") (pin "9") (pinfunction "AD0/SDO_9") (pintype "bidirectional"))
    )
    (net (code "41") (name "GPIO13") (class "Default")
      (node (ref "Q5") (pin "3") (pinfunction "D_3") (pintype "bidirectional"))
      (node (ref "R17") (pin "1") (pinfunction "1_1") (pintype "passive"))
      (node (ref "U3") (pin "16") (pinfunction "IO13_16") (pintype "bidirectional"))
    )
    (net (code "42") (name "GPIO13{slash}SDI") (class "Default")
      (node (ref "Q5") (pin "2") (pinfunction "S_2") (pintype "bidirectional"))
      (node (ref "R16") (pin "1") (pinfunction "1_1") (pintype "passive"))
      (node (ref "U1") (pin "24") (pinfunction "SDA/SDI_24") (pintype "bidirectional"))
    )
    (net (code "43") (name "GPIO15") (class "Default")
      (node (ref "Q10") (pin "3") (pinfunction "D_3") (pintype "bidirectional"))
      (node (ref "R2") (pin "1") (pinfunction "1_1") (pintype "passive"))
      (node (ref "U3") (pin "23") (pinfunction "IO15_23") (pintype "bidirectional"))
    )
    (net (code "44") (name "GPIO15{slash}CS") (class "Default")
      (node (ref "Q10") (pin "2") (pinfunction "S_2") (pintype "bidirectional"))
      (node (ref "R29") (pin "1") (pinfunction "1_1") (pintype "passive"))
      (node (ref "U1") (pin "22") (pinfunction "~{CS}_22") (pintype "bidirectional"))
    )
    (net (code "45") (name "Net-(C12-Pad1)") (class "Default")
      (node (ref "C12") (pin "1") (pinfunction "1_1") (pintype "passive"))
      (node (ref "U$5") (pin "C-") (pinfunction "C-_C-") (pintype "bidirectional"))
    )
    (net (code "46") (name "Net-(C12-Pad2)") (class "Default")
      (node (ref "C12") (pin "2") (pinfunction "2_2") (pintype "passive"))
      (node (ref "U$5") (pin "C+") (pinfunction "C+_C+") (pintype "bidirectional"))
    )
    (net (code "47") (name "Net-(Q1-B)") (class "Default")
      (node (ref "Q1") (pin "1") (pinfunction "B_1") (pintype "passive"))
      (node (ref "R3") (pin "2") (pinfunction "2_2") (pintype "passive"))
    )
    (net (code "48") (name "Net-(Q4-B)") (class "Default")
      (node (ref "Q4") (pin "1") (pinfunction "B_1") (pintype "passive"))
      (node (ref "R24") (pin "2") (pinfunction "2_2") (pintype "passive"))
    )
    (net (code "49") (name "Net-(R1-Pad1)") (class "Default")
      (node (ref "R1") (pin "1") (pinfunction "1_1") (pintype "passive"))
      (node (ref "U5") (pin "EXTON") (pinfunction "EXTON_EXTON") (pintype "bidirectional"))
    )
    (net (code "50") (name "Net-(R7-Pad1)") (class "Default")
      (node (ref "R7") (pin "1") (pinfunction "1_1") (pintype "passive"))
      (node (ref "U$6") (pin "1") (pinfunction "1_1") (pintype "bidirectional"))
    )
    (net (code "51") (name "Net-(R8-Pad1)") (class "Default")
      (node (ref "R8") (pin "1") (pinfunction "1_1") (pintype "passive"))
      (node (ref "U$9") (pin "1") (pinfunction "1_1") (pintype "bidirectional"))
    )
    (net (code "52") (name "Net-(R12-Pad2)") (class "Default")
      (node (ref "R12") (pin "2") (pinfunction "2_2") (pintype "passive"))
      (node (ref "U$10") (pin "A5") (pinfunction "A5_A5") (pintype "bidirectional"))
    )
    (net (code "53") (name "Net-(R15-Pad2)") (class "Default")
      (node (ref "R15") (pin "2") (pinfunction "2_2") (pintype "passive"))
      (node (ref "U$5") (pin "EN") (pinfunction "EN_EN") (pintype "bidirectional"))
    )
    (net (code "54") (name "Net-(R25-Pad1)") (class "Default")
      (node (ref "R25") (pin "1") (pinfunction "1_1") (pintype "passive"))
      (node (ref "U5") (pin "WAKEUP") (pinfunction "WAKEUP_WAKEUP") (pintype "bidirectional"))
    )
    (net (code "55") (name "Net-(R27-Pad2)") (class "Default")
      (node (ref "R27") (pin "2") (pinfunction "2_2") (pintype "passive"))
      (node (ref "U$10") (pin "B5") (pinfunction "B5_B5") (pintype "bidirectional"))
    )
    (net (code "56") (name "Net-(U$2-P$1)") (class "Default")
      (node (ref "U$2") (pin "1") (pinfunction "P$1_1") (pintype "bidirectional"))
      (node (ref "U$4") (pin "4") (pinfunction "FB_4") (pintype "bidirectional"))
      (node (ref "U$4") (pin "5") (pinfunction "SW_5") (pintype "bidirectional"))
    )
    (net (code "57") (name "Net-(U1-REGOUT)") (class "Default")
      (node (ref "C9") (pin "1") (pinfunction "1_1") (pintype "passive"))
      (node (ref "U1") (pin "10") (pinfunction "REGOUT_10") (pintype "bidirectional"))
    )
    (net (code "58") (name "Net-(U2-PROG)") (class "Default")
      (node (ref "R6") (pin "2") (pinfunction "2_2") (pintype "passive"))
      (node (ref "U2") (pin "5") (pinfunction "PROG_5") (pintype "input"))
    )
    (net (code "59") (name "Net-(U2-STAT)") (class "Default")
      (node (ref "U$6") (pin "2") (pinfunction "2_2") (pintype "bidirectional"))
      (node (ref "U2") (pin "1") (pinfunction "STAT_1") (pintype "output"))
    )
    (net (code "60") (name "Net-(U5-RSTN)") (class "Default")
      (node (ref "R13") (pin "1") (pinfunction "1_1") (pintype "passive"))
      (node (ref "U5") (pin "RST") (pinfunction "RSTN_RST") (pintype "bidirectional"))
    )
    (net (code "61") (name "VIN") (class "Default")
      (node (ref "C16") (pin "1") (pinfunction "1_1") (pintype "passive"))
      (node (ref "C19") (pin "1") (pinfunction "1_1") (pintype "passive"))
      (node (ref "D1") (pin "1") (pinfunction "K_1") (pintype "bidirectional"))
      (node (ref "Q3") (pin "2") (pinfunction "S_2") (pintype "bidirectional"))
      (node (ref "R15") (pin "1") (pinfunction "1_1") (pintype "passive"))
      (node (ref "U$4") (pin "1") (pinfunction "VI_1") (pintype "bidirectional"))
      (node (ref "U$4") (pin "3") (pinfunction "EN_3") (pintype "bidirectional"))
      (node (ref "U$5") (pin "VIN") (pinfunction "VIN_VIN") (pintype "bidirectional"))
    )
    (net (code "62") (name "V_BATT") (class "Default")
      (node (ref "C17") (pin "1") (pinfunction "1_1") (pintype "passive"))
      (node (ref "Q3") (pin "3") (pinfunction "D_3") (pintype "bidirectional"))
      (node (ref "U$8") (pin "4") (pinfunction "+_4") (pintype "bidirectional"))
      (node (ref "U2") (pin "3") (pinfunction "VBAT_3") (pintype "power_in"))
    )
    (net (code "63") (name "V_USB") (class "Default")
      (node (ref "C13") (pin "1") (pinfunction "1_1") (pintype "passive"))
      (node (ref "D1") (pin "2") (pinfunction "A_2") (pintype "bidirectional"))
      (node (ref "Q3") (pin "1") (pinfunction "G_1") (pintype "bidirectional"))
      (node (ref "R11") (pin "2") (pinfunction "2_2") (pintype "passive"))
      (node (ref "R7") (pin "2") (pinfunction "2_2") (pintype "passive"))
      (node (ref "U$10") (pin "A4") (pinfunction "A4_A4") (pintype "bidirectional"))
      (node (ref "U$7") (pin "1") (pinfunction "1_1") (pintype "bidirectional"))
      (node (ref "U2") (pin "4") (pinfunction "VIN_4") (pintype "power_in"))
    )
    (net (code "64") (name "unconnected-(U$7-Pad4)") (class "Default")
      (node (ref "U$7") (pin "4") (pinfunction "4_4") (pintype "bidirectional"))
    )
    (net (code "65") (name "unconnected-(U$7-Pad5)") (class "Default")
      (node (ref "U$7") (pin "5") (pinfunction "5_5") (pintype "bidirectional"))
    )
    (net (code "66") (name "unconnected-(U$10-PadA1)") (class "Default")
      (node (ref "U$10") (pin "A1") (pinfunction "A1_A1") (pintype "bidirectional"))
    )
    (net (code "67") (name "unconnected-(U$10-PadA8)") (class "Default")
      (node (ref "U$10") (pin "A8") (pinfunction "A8_A8") (pintype "bidirectional"))
    )
    (net (code "68") (name "unconnected-(U$10-PadA9)") (class "Default")
      (node (ref "U$10") (pin "A9") (pinfunction "A9_A9") (pintype "bidirectional"))
    )
    (net (code "69") (name "unconnected-(U$10-PadB8)") (class "Default")
      (node (ref "U$10") (pin "B8") (pinfunction "B8_B8") (pintype "bidirectional"))
    )
    (net (code "70") (name "unconnected-(U$11-CTS-Pad9)") (class "Default")
      (node (ref "U$11") (pin "9") (pinfunction "CTS_9") (pintype "bidirectional"))
    )
    (net (code "71") (name "unconnected-(U$11-DCD-Pad12)") (class "Default")
      (node (ref "U$11") (pin "12") (pinfunction "DCD_12") (pintype "bidirectional"))
    )
    (net (code "72") (name "unconnected-(U$11-DSR-Pad10)") (class "Default")
      (node (ref "U$11") (pin "10") (pinfunction "DSR_10") (pintype "bidirectional"))
    )
    (net (code "73") (name "unconnected-(U$11-NC-Pad8)") (class "Default")
      (node (ref "U$11") (pin "8") (pinfunction "NC_8") (pintype "bidirectional"))
    )
    (net (code "74") (name "unconnected-(U$11-RI-Pad11)") (class "Default")
      (node (ref "U$11") (pin "11") (pinfunction "RI_11") (pintype "bidirectional"))
    )
    (net (code "75") (name "unconnected-(U$11-RST-Pad7)") (class "Default")
      (node (ref "U$11") (pin "7") (pinfunction "RST_7") (pintype "bidirectional"))
    )
    (net (code "76") (name "unconnected-(U$11-TNOW-Pad15)") (class "Default")
      (node (ref "U$11") (pin "15") (pinfunction "TNOW_15") (pintype "bidirectional"))
    )
    (net (code "77") (name "unconnected-(U1-AUX_CL-Pad7)") (class "Default")
      (node (ref "U1") (pin "7") (pinfunction "AUX_CL_7") (pintype "bidirectional"))
    )
    (net (code "78") (name "unconnected-(U1-AUX_DA-Pad21)") (class "Default")
      (node (ref "U1") (pin "21") (pinfunction "AUX_DA_21") (pintype "bidirectional"))
    )
    (net (code "79") (name "unconnected-(U3-CLK-Pad20)") (class "Default")
      (node (ref "U3") (pin "20") (pinfunction "CLK_20") (pintype "bidirectional"))
    )
    (net (code "80") (name "unconnected-(U3-CMD-Pad19)") (class "Default")
      (node (ref "U3") (pin "19") (pinfunction "CMD_19") (pintype "bidirectional"))
    )
    (net (code "81") (name "unconnected-(U3-NC-Pad32)") (class "Default")
      (node (ref "U3") (pin "32") (pinfunction "NC_32") (pintype "bidirectional"))
    )
    (net (code "82") (name "unconnected-(U3-PadGND)") (class "Default")
      (node (ref "U3") (pin "GND") (pinfunction "GND_GND") (pintype "bidirectional"))
    )
    (net (code "83") (name "unconnected-(U3-SD1-Pad22)") (class "Default")
      (node (ref "U3") (pin "22") (pinfunction "SD1_22") (pintype "bidirectional"))
    )
    (net (code "84") (name "unconnected-(U3-SD2-Pad17)") (class "Default")
      (node (ref "U3") (pin "17") (pinfunction "SD2_17") (pintype "bidirectional"))
    )
    (net (code "85") (name "unconnected-(U3-SD3-Pad18)") (class "Default")
      (node (ref "U3") (pin "18") (pinfunction "SD3_18") (pintype "bidirectional"))
    )
    (net (code "86") (name "unconnected-(U3-SDO-Pad21)") (class "Default")
      (node (ref "U3") (pin "21") (pinfunction "SDO_21") (pintype "bidirectional"))
    )
    (net (code "87") (name "unconnected-(U5-PadGPIO0)") (class "Default")
      (node (ref "U5") (pin "GPIO0") (pinfunction "GPIO0_GPIO0") (pintype "bidirectional"))
    )
    (net (code "88") (name "unconnected-(U5-PadGPIO1)") (class "Default")
      (node (ref "U5") (pin "GPIO1") (pinfunction "GPIO1_GPIO1") (pintype "bidirectional"))
    )
    (net (code "89") (name "unconnected-(U5-PadGPIO2)") (class "Default")
      (node (ref "U5") (pin "GPIO2") (pinfunction "GPIO2_GPIO2") (pintype "bidirectional"))
    )
  )
)
